# SPI_IFC.net
KiCad netlist of a schematic drawn in Altium Designer
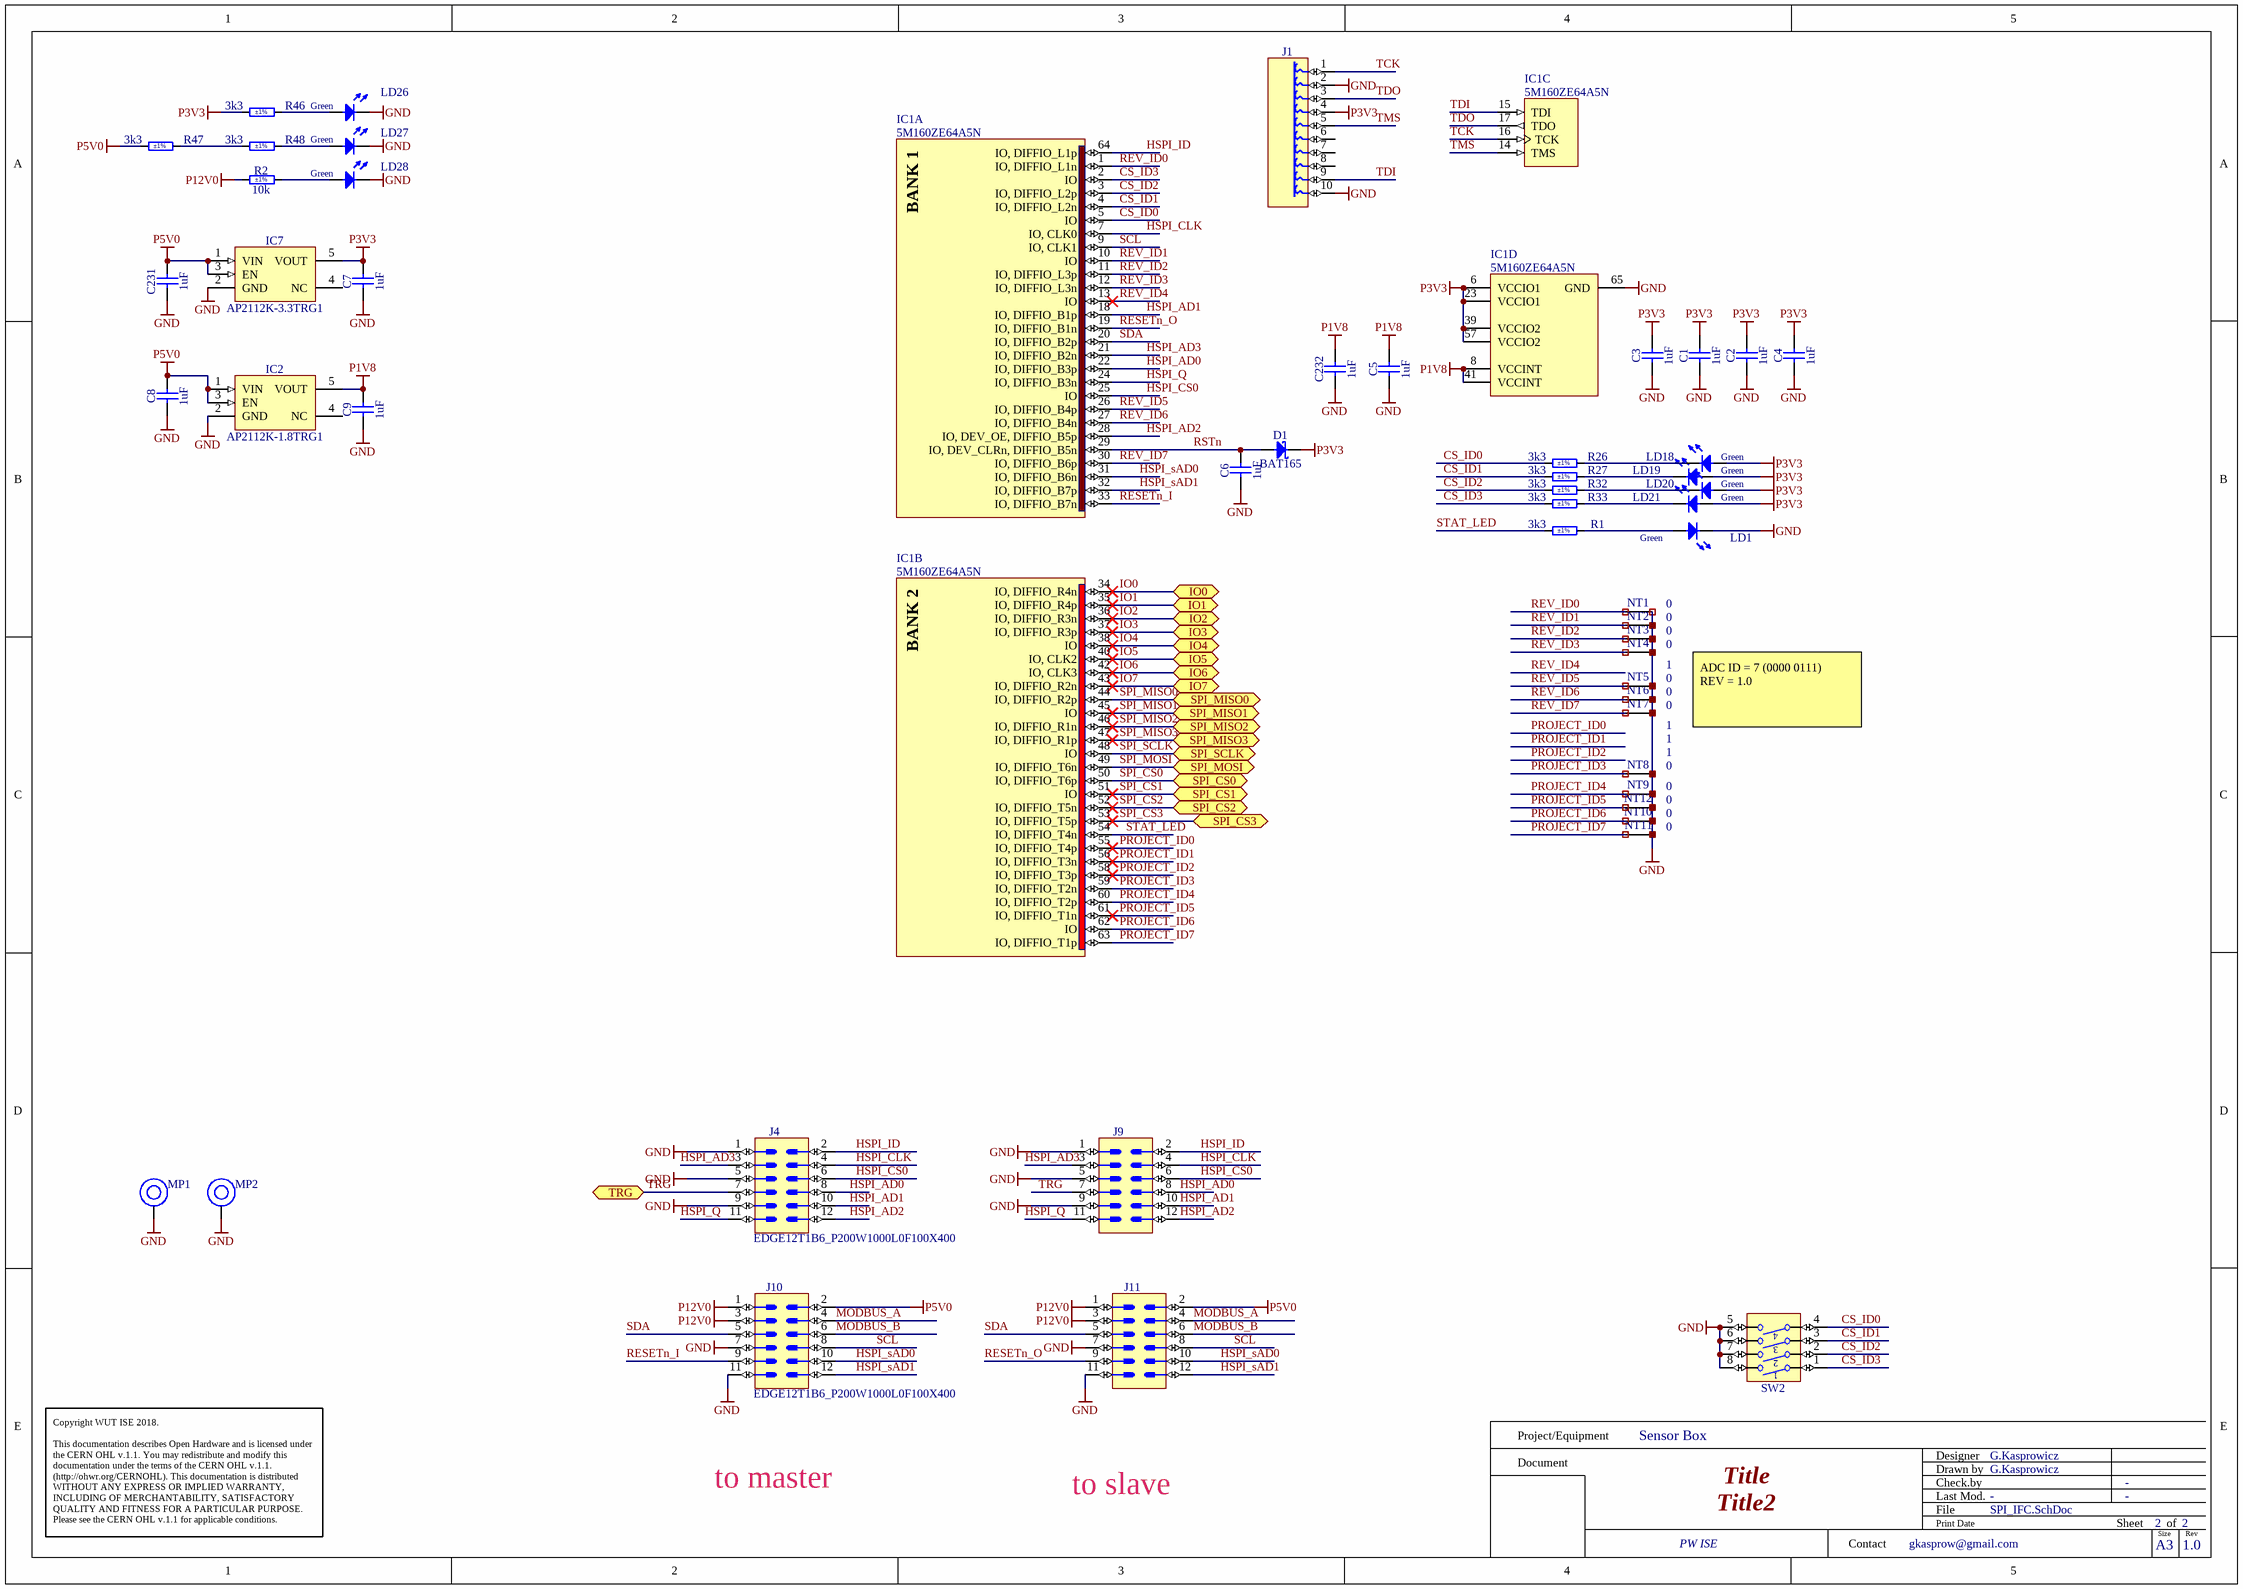
[diagram p0: SPI_IFC.SchDoc]

(export (version "E")
  (design (tool "Eeschema 10.0.6"))
  (components
    (comp (ref "C1")
      (value "1uF")
      (footprint "CAPC1005X55N")
      (description "Non-polarised capacitor")
      (fields
        (field (name "PART NUMBER") "CC0402_1UF_16V_10%_X5R")
        (field (name "VOLTAGE") "16V")
        (field (name "AUTHOR") "CERN DEM JLC")
      )
      (libsource (lib "Capacitors") (part "Capacitor - non polarized"))
    )
    (comp (ref "C2")
      (value "1uF")
      (footprint "CAPC1005X55N")
      (description "Non-polarised capacitor")
      (fields
        (field (name "PART NUMBER") "CC0402_1UF_16V_10%_X5R")
        (field (name "VOLTAGE") "16V")
        (field (name "AUTHOR") "CERN DEM JLC")
      )
      (libsource (lib "Capacitors") (part "Capacitor - non polarized"))
    )
    (comp (ref "C3")
      (value "1uF")
      (footprint "CAPC1005X55N")
      (description "Non-polarised capacitor")
      (fields
        (field (name "PART NUMBER") "CC0402_1UF_16V_10%_X5R")
        (field (name "VOLTAGE") "16V")
        (field (name "AUTHOR") "CERN DEM JLC")
      )
      (libsource (lib "Capacitors") (part "Capacitor - non polarized"))
    )
    (comp (ref "C4")
      (value "1uF")
      (footprint "CAPC1005X55N")
      (description "Non-polarised capacitor")
      (fields
        (field (name "PART NUMBER") "CC0402_1UF_16V_10%_X5R")
        (field (name "VOLTAGE") "16V")
        (field (name "AUTHOR") "CERN DEM JLC")
      )
      (libsource (lib "Capacitors") (part "Capacitor - non polarized"))
    )
    (comp (ref "C5")
      (value "1uF")
      (footprint "CAPC1005X55N")
      (description "Non-polarised capacitor")
      (fields
        (field (name "PART NUMBER") "CC0402_1UF_16V_10%_X5R")
        (field (name "VOLTAGE") "16V")
        (field (name "AUTHOR") "CERN DEM JLC")
      )
      (libsource (lib "Capacitors") (part "Capacitor - non polarized"))
    )
    (comp (ref "C6")
      (value "1uF")
      (footprint "CAPC1005X55N")
      (description "Non-polarised capacitor")
      (fields
        (field (name "PART NUMBER") "CC0402_1UF_16V_10%_X5R")
        (field (name "VOLTAGE") "16V")
        (field (name "AUTHOR") "CERN DEM JLC")
      )
      (libsource (lib "Capacitors") (part "Capacitor - non polarized"))
    )
    (comp (ref "C7")
      (value "1uF")
      (footprint "CAPC1005X55N")
      (description "Non-polarised capacitor")
      (fields
        (field (name "PART NUMBER") "CC0402_1UF_16V_10%_X5R")
        (field (name "VOLTAGE") "16V")
        (field (name "AUTHOR") "CERN DEM JLC")
      )
      (libsource (lib "Capacitors") (part "Capacitor - non polarized"))
    )
    (comp (ref "C8")
      (value "1uF")
      (footprint "CAPC1005X55N")
      (description "Non-polarised capacitor")
      (fields
        (field (name "PART NUMBER") "CC0402_1UF_16V_10%_X5R")
        (field (name "VOLTAGE") "16V")
        (field (name "AUTHOR") "CERN DEM JLC")
      )
      (libsource (lib "Capacitors") (part "Capacitor - non polarized"))
    )
    (comp (ref "C9")
      (value "1uF")
      (footprint "CAPC1005X55N")
      (description "Non-polarised capacitor")
      (fields
        (field (name "PART NUMBER") "CC0402_1UF_16V_10%_X5R")
        (field (name "VOLTAGE") "16V")
        (field (name "AUTHOR") "CERN DEM JLC")
      )
      (libsource (lib "Capacitors") (part "Capacitor - non polarized"))
    )
    (comp (ref "C231")
      (value "1uF")
      (footprint "CAPC1005X55N")
      (description "Non-polarised capacitor")
      (fields
        (field (name "PART NUMBER") "CC0402_1UF_16V_10%_X5R")
        (field (name "VOLTAGE") "16V")
        (field (name "AUTHOR") "CERN DEM JLC")
      )
      (libsource (lib "Capacitors") (part "Capacitor - non polarized"))
    )
    (comp (ref "C232")
      (value "1uF")
      (footprint "CAPC1005X55N")
      (description "Non-polarised capacitor")
      (fields
        (field (name "PART NUMBER") "CC0402_1UF_16V_10%_X5R")
        (field (name "VOLTAGE") "16V")
        (field (name "AUTHOR") "CERN DEM JLC")
      )
      (libsource (lib "Capacitors") (part "Capacitor - non polarized"))
    )
    (comp (ref "D1")
      (value "BAT165")
      (footprint "SOD2512X110N")
      (description "Schottky Diode")
      (fields
        (field (name "VOLTAGE") "40V")
        (field (name "POWER") "750mA")
        (field (name "AUTHOR") "CERN DEM JLC")
      )
      (libsource (lib "ICs And Semiconductors") (part "Diode Schottky"))
    )
    (comp (ref "IC1")
      (value "5M160ZE64A5N")
      (footprint "QFP40P900X900X120-65N-S550")
      (fields (field (name "MANUFACTURER") "ALTERA") (field (name "AUTHOR") "CERN DEM JLC"))
      (libsource (lib "ICs And Semiconductors") (part "5M160ZE64A5N"))
    )
    (comp (ref "IC2")
      (value "AP2112K-1.8TRG1")
      (footprint "SOT95P285X140-5N")
      (description "600mA CMOS Low Dropout Linear Regulator with Enable")
      (fields
        (field (name "MANUFACTURER") "DIODES INCORPORATED")
        (field (name "MANUFACTURER PART NUMBER") "AP2112K-1.8")
        (field (name "AUTHOR") "CERN DEM JLC")
      )
      (libsource (lib "ICs And Semiconductors") (part "AP2112K"))
    )
    (comp (ref "IC7")
      (value "AP2112K-3.3TRG1")
      (footprint "SOT95P285X140-5N")
      (description "600mA CMOS Low Dropout Linear Regulator with Enable")
      (fields
        (field (name "MANUFACTURER") "DIODES INCORPORATED")
        (field (name "MANUFACTURER PART NUMBER") "AP2112K-3.3")
        (field (name "AUTHOR") "CERN DEM MR")
      )
      (libsource (lib "ICs And Semiconductors") (part "AP2112K"))
    )
    (comp (ref "J1")
      (value "TC2050-IDC")
      (footprint "TC2050-IDC")
      (description "TC2030-MCP and TC2050-IDC Pad Contact")
      (fields (field (name "AUTHOR") "CERN DEM HF"))
      (libsource (lib "Eletro-mechanical") (part "TC2050-IDC"))
    )
    (comp (ref "J4")
      (value "~")
      (footprint "EDGE12T1B6_P200W1000L0F100X400")
      (description "PCB Edge Connector 12 (2x6)")
      (fields
        (field (name "PART NUMBER") "EDGE10T1B6_P200W1000L0F100X400")
        (field (name "AUTHOR") "CERN DEM MR")
      )
      (libsource (lib "Connectors") (part "PCB Edge Connector 12 (2x6)"))
    )
    (comp (ref "J9")
      (value "~")
      (footprint "EDGE12T5B10_P200W1000L0F100X400")
      (description "PCB Edge Connector 12 (2x6)")
      (fields (field (name "PART NUMBER") "EDGE12T5B10_P200W1000L0F100X400") (field (name "AUTHOR") "GK"))
      (libsource (lib "Connectors") (part "PCB Edge Connector 12 (2x6) R"))
    )
    (comp (ref "J10")
      (value "~")
      (footprint "EDGE12T1B6_P200W1000L0F100X400")
      (description "PCB Edge Connector 12 (2x6)")
      (fields
        (field (name "PART NUMBER") "EDGE10T1B6_P200W1000L0F100X400")
        (field (name "AUTHOR") "CERN DEM MR")
      )
      (libsource (lib "Connectors") (part "PCB Edge Connector 12 (2x6)"))
    )
    (comp (ref "J11")
      (value "~")
      (footprint "EDGE12T5B10_P200W1000L0F100X400")
      (description "PCB Edge Connector 12 (2x6)")
      (fields (field (name "PART NUMBER") "EDGE12T5B10_P200W1000L0F100X400") (field (name "AUTHOR") "GK"))
      (libsource (lib "Connectors") (part "PCB Edge Connector 12 (2x6) R"))
    )
    (comp (ref "LD1")
      (value "Green")
      (footprint "LED_KINGBRIGHT_KP-1608CGCK")
      (description "LED Green 1C 2A")
      (fields
        (field (name "PART NUMBER") "LED_KINGBRIGHT_KP-1608CGCK")
        (field (name "MANUFACTURER") "KINGBRIGHT")
        (field (name "AUTHOR") "CERN DEM HF")
      )
      (libsource (lib "ICs And Semiconductors") (part "LED Green 1C 2A"))
    )
    (comp (ref "LD18")
      (value "Green")
      (footprint "LED_KINGBRIGHT_KP-1608CGCK")
      (description "LED Green 1C 2A")
      (fields
        (field (name "PART NUMBER") "LED_KINGBRIGHT_KP-1608CGCK")
        (field (name "MANUFACTURER") "KINGBRIGHT")
        (field (name "AUTHOR") "CERN DEM HF")
      )
      (libsource (lib "ICs And Semiconductors") (part "LED Green 1C 2A"))
    )
    (comp (ref "LD19")
      (value "Green")
      (footprint "LED_KINGBRIGHT_KP-1608CGCK")
      (description "LED Green 1C 2A")
      (fields
        (field (name "PART NUMBER") "LED_KINGBRIGHT_KP-1608CGCK")
        (field (name "MANUFACTURER") "KINGBRIGHT")
        (field (name "AUTHOR") "CERN DEM HF")
      )
      (libsource (lib "ICs And Semiconductors") (part "LED Green 1C 2A"))
    )
    (comp (ref "LD20")
      (value "Green")
      (footprint "LED_KINGBRIGHT_KP-1608CGCK")
      (description "LED Green 1C 2A")
      (fields
        (field (name "PART NUMBER") "LED_KINGBRIGHT_KP-1608CGCK")
        (field (name "MANUFACTURER") "KINGBRIGHT")
        (field (name "AUTHOR") "CERN DEM HF")
      )
      (libsource (lib "ICs And Semiconductors") (part "LED Green 1C 2A"))
    )
    (comp (ref "LD21")
      (value "Green")
      (footprint "LED_KINGBRIGHT_KP-1608CGCK")
      (description "LED Green 1C 2A")
      (fields
        (field (name "PART NUMBER") "LED_KINGBRIGHT_KP-1608CGCK")
        (field (name "MANUFACTURER") "KINGBRIGHT")
        (field (name "AUTHOR") "CERN DEM HF")
      )
      (libsource (lib "ICs And Semiconductors") (part "LED Green 1C 2A"))
    )
    (comp (ref "LD26")
      (value "Green")
      (footprint "LED_KINGBRIGHT_KP-1608CGCK")
      (description "LED Green 1C 2A")
      (fields
        (field (name "PART NUMBER") "LED_KINGBRIGHT_KP-1608CGCK")
        (field (name "MANUFACTURER") "KINGBRIGHT")
        (field (name "AUTHOR") "CERN DEM HF")
      )
      (libsource (lib "ICs And Semiconductors") (part "LED Green 1C 2A"))
    )
    (comp (ref "LD27")
      (value "Green")
      (footprint "LED_KINGBRIGHT_KP-1608CGCK")
      (description "LED Green 1C 2A")
      (fields
        (field (name "PART NUMBER") "LED_KINGBRIGHT_KP-1608CGCK")
        (field (name "MANUFACTURER") "KINGBRIGHT")
        (field (name "AUTHOR") "CERN DEM HF")
      )
      (libsource (lib "ICs And Semiconductors") (part "LED Green 1C 2A"))
    )
    (comp (ref "LD28")
      (value "Green")
      (footprint "LED_KINGBRIGHT_KP-1608CGCK")
      (description "LED Green 1C 2A")
      (fields
        (field (name "PART NUMBER") "LED_KINGBRIGHT_KP-1608CGCK")
        (field (name "MANUFACTURER") "KINGBRIGHT")
        (field (name "AUTHOR") "CERN DEM HF")
      )
      (libsource (lib "ICs And Semiconductors") (part "LED Green 1C 2A"))
    )
    (comp (ref "MP1")
      (value "M1.6 x 3mm")
      (footprint "97730306330")
      (description "WA-SMSI SMT Steel Spacer with internal Thread Bottom closed, OD 3.3mm, M1.6 x 3mm")
      (fields
        (field (name "MANUFACTURER PART NUMBER") "97730306330R")
        (field (name "MANUFACTURER") "Wurth Elektronik")
      )
      (libsource (lib "Altium_WA-SMSI (rev22a)") (part "97730306330R"))
    )
    (comp (ref "MP2")
      (value "M1.6 x 3mm")
      (footprint "97730306330")
      (description "WA-SMSI SMT Steel Spacer with internal Thread Bottom closed, OD 3.3mm, M1.6 x 3mm")
      (fields
        (field (name "MANUFACTURER PART NUMBER") "97730306330R")
        (field (name "MANUFACTURER") "Wurth Elektronik")
      )
      (libsource (lib "Altium_WA-SMSI (rev22a)") (part "97730306330R"))
    )
    (comp (ref "NT1")
      (value "Net Tie")
      (footprint "Net Tie 3")
      (fields (field (name "PART NUMBER") "Net Tie 3") (field (name "AUTHOR") "CERN DEM HF"))
      (libsource (lib "Eletro-mechanical") (part "Net Tie_a"))
    )
    (comp (ref "NT2")
      (value "Net Tie")
      (footprint "Net Tie 3")
      (fields (field (name "PART NUMBER") "Net Tie 3") (field (name "AUTHOR") "CERN DEM HF"))
      (libsource (lib "Eletro-mechanical") (part "Net Tie_a"))
    )
    (comp (ref "NT3")
      (value "Net Tie")
      (footprint "Net Tie 3")
      (fields (field (name "PART NUMBER") "Net Tie 3") (field (name "AUTHOR") "CERN DEM HF"))
      (libsource (lib "Eletro-mechanical") (part "Net Tie_a"))
    )
    (comp (ref "NT4")
      (value "Net Tie")
      (footprint "Net Tie 3")
      (fields (field (name "PART NUMBER") "Net Tie 3") (field (name "AUTHOR") "CERN DEM HF"))
      (libsource (lib "Eletro-mechanical") (part "Net Tie_a"))
    )
    (comp (ref "NT5")
      (value "Net Tie")
      (footprint "Net Tie 3")
      (fields (field (name "PART NUMBER") "Net Tie 3") (field (name "AUTHOR") "CERN DEM HF"))
      (libsource (lib "Eletro-mechanical") (part "Net Tie_a"))
    )
    (comp (ref "NT6")
      (value "Net Tie")
      (footprint "Net Tie 3")
      (fields (field (name "PART NUMBER") "Net Tie 3") (field (name "AUTHOR") "CERN DEM HF"))
      (libsource (lib "Eletro-mechanical") (part "Net Tie_a"))
    )
    (comp (ref "NT7")
      (value "Net Tie")
      (footprint "Net Tie 3")
      (fields (field (name "PART NUMBER") "Net Tie 3") (field (name "AUTHOR") "CERN DEM HF"))
      (libsource (lib "Eletro-mechanical") (part "Net Tie_a"))
    )
    (comp (ref "NT8")
      (value "Net Tie")
      (footprint "Net Tie 3")
      (fields (field (name "PART NUMBER") "Net Tie 3") (field (name "AUTHOR") "CERN DEM HF"))
      (libsource (lib "Eletro-mechanical") (part "Net Tie_a"))
    )
    (comp (ref "NT9")
      (value "Net Tie")
      (footprint "Net Tie 3")
      (fields (field (name "PART NUMBER") "Net Tie 3") (field (name "AUTHOR") "CERN DEM HF"))
      (libsource (lib "Eletro-mechanical") (part "Net Tie_a"))
    )
    (comp (ref "NT10")
      (value "Net Tie")
      (footprint "Net Tie 3")
      (fields (field (name "PART NUMBER") "Net Tie 3") (field (name "AUTHOR") "CERN DEM HF"))
      (libsource (lib "Eletro-mechanical") (part "Net Tie_a"))
    )
    (comp (ref "NT11")
      (value "Net Tie")
      (footprint "Net Tie 3")
      (fields (field (name "PART NUMBER") "Net Tie 3") (field (name "AUTHOR") "CERN DEM HF"))
      (libsource (lib "Eletro-mechanical") (part "Net Tie_a"))
    )
    (comp (ref "NT12")
      (value "Net Tie")
      (footprint "Net Tie 3")
      (fields (field (name "PART NUMBER") "Net Tie 3") (field (name "AUTHOR") "CERN DEM HF"))
      (libsource (lib "Eletro-mechanical") (part "Net Tie_a"))
    )
    (comp (ref "R1")
      (value "3k3")
      (footprint "RESC1005X40N")
      (description "Resistor - 1%")
      (fields
        (field (name "TOLERANCE") "±1%")
        (field (name "PART NUMBER") "R0402_3K3_1%_0.0625W_100PPM")
        (field (name "POWER") "0.0625W")
        (field (name "AUTHOR") "CERN DEM JLC")
      )
      (libsource (lib "Resistors") (part "Resistor - 1%"))
    )
    (comp (ref "R2")
      (value "10k")
      (footprint "RESC1005X40N")
      (description "Resistor - 1%")
      (fields
        (field (name "TOLERANCE") "±1%")
        (field (name "PART NUMBER") "R0402_10K_1%_0.0625W_100PPM")
        (field (name "POWER") "0.0625W")
        (field (name "AUTHOR") "CERN DEM JLC")
      )
      (libsource (lib "Resistors") (part "Resistor - 1%"))
    )
    (comp (ref "R26")
      (value "3k3")
      (footprint "RESC1005X40N")
      (description "Resistor - 1%")
      (fields
        (field (name "TOLERANCE") "±1%")
        (field (name "PART NUMBER") "R0402_3K3_1%_0.0625W_100PPM")
        (field (name "POWER") "0.0625W")
        (field (name "AUTHOR") "CERN DEM JLC")
      )
      (libsource (lib "Resistors") (part "Resistor - 1%"))
    )
    (comp (ref "R27")
      (value "3k3")
      (footprint "RESC1005X40N")
      (description "Resistor - 1%")
      (fields
        (field (name "TOLERANCE") "±1%")
        (field (name "PART NUMBER") "R0402_3K3_1%_0.0625W_100PPM")
        (field (name "POWER") "0.0625W")
        (field (name "AUTHOR") "CERN DEM JLC")
      )
      (libsource (lib "Resistors") (part "Resistor - 1%"))
    )
    (comp (ref "R32")
      (value "3k3")
      (footprint "RESC1005X40N")
      (description "Resistor - 1%")
      (fields
        (field (name "TOLERANCE") "±1%")
        (field (name "PART NUMBER") "R0402_3K3_1%_0.0625W_100PPM")
        (field (name "POWER") "0.0625W")
        (field (name "AUTHOR") "CERN DEM JLC")
      )
      (libsource (lib "Resistors") (part "Resistor - 1%"))
    )
    (comp (ref "R33")
      (value "3k3")
      (footprint "RESC1005X40N")
      (description "Resistor - 1%")
      (fields
        (field (name "TOLERANCE") "±1%")
        (field (name "PART NUMBER") "R0402_3K3_1%_0.0625W_100PPM")
        (field (name "POWER") "0.0625W")
        (field (name "AUTHOR") "CERN DEM JLC")
      )
      (libsource (lib "Resistors") (part "Resistor - 1%"))
    )
    (comp (ref "R46")
      (value "3k3")
      (footprint "RESC1005X40N")
      (description "Resistor - 1%")
      (fields
        (field (name "TOLERANCE") "±1%")
        (field (name "PART NUMBER") "R0402_3K3_1%_0.0625W_100PPM")
        (field (name "POWER") "0.0625W")
        (field (name "AUTHOR") "CERN DEM JLC")
      )
      (libsource (lib "Resistors") (part "Resistor - 1%"))
    )
    (comp (ref "R47")
      (value "3k3")
      (footprint "RESC1005X40N")
      (description "Resistor - 1%")
      (fields
        (field (name "TOLERANCE") "±1%")
        (field (name "PART NUMBER") "R0402_3K3_1%_0.0625W_100PPM")
        (field (name "POWER") "0.0625W")
        (field (name "AUTHOR") "CERN DEM JLC")
      )
      (libsource (lib "Resistors") (part "Resistor - 1%"))
    )
    (comp (ref "R48")
      (value "3k3")
      (footprint "RESC1005X40N")
      (description "Resistor - 1%")
      (fields
        (field (name "TOLERANCE") "±1%")
        (field (name "PART NUMBER") "R0402_3K3_1%_0.0625W_100PPM")
        (field (name "POWER") "0.0625W")
        (field (name "AUTHOR") "CERN DEM JLC")
      )
      (libsource (lib "Resistors") (part "Resistor - 1%"))
    )
    (comp (ref "SW2")
      (value "Switch")
      (footprint "SW_OMRON_A6H-4102")
      (description "4 Ways SPST DIP Switch")
      (fields
        (field (name "PART NUMBER") "SW_OMRON_A6H-4102")
        (field (name "MANUFACTURER") "OMRON")
        (field (name "AUTHOR") "CERN DEM JLC")
      )
      (libsource (lib "Eletro-mechanical") (part "SW 4x SPST DIP Switch"))
    )
  )
  (nets
    (net (code "1") (name "/CS_ID0") (class "Default")
      (node (ref "IC1") (pin "5") (pinfunction "IO_5") (pintype "bidirectional"))
      (node (ref "R26") (pin "2") (pinfunction "2_2") (pintype "passive"))
      (node (ref "SW2") (pin "4") (pinfunction "4_4") (pintype "bidirectional"))
    )
    (net (code "2") (name "/CS_ID1") (class "Default")
      (node (ref "IC1") (pin "4") (pinfunction "IO,_DIFFIO_L2n_4") (pintype "bidirectional"))
      (node (ref "R27") (pin "2") (pinfunction "2_2") (pintype "passive"))
      (node (ref "SW2") (pin "3") (pinfunction "3_3") (pintype "bidirectional"))
    )
    (net (code "3") (name "/CS_ID2") (class "Default")
      (node (ref "IC1") (pin "3") (pinfunction "IO,_DIFFIO_L2p_3") (pintype "bidirectional"))
      (node (ref "R32") (pin "2") (pinfunction "2_2") (pintype "passive"))
      (node (ref "SW2") (pin "2") (pinfunction "2_2") (pintype "bidirectional"))
    )
    (net (code "4") (name "/CS_ID3") (class "Default")
      (node (ref "IC1") (pin "2") (pinfunction "IO_2") (pintype "bidirectional"))
      (node (ref "R33") (pin "2") (pinfunction "2_2") (pintype "passive"))
      (node (ref "SW2") (pin "1") (pinfunction "1_1") (pintype "bidirectional"))
    )
    (net (code "5") (name "/HSPI_AD0") (class "Default")
      (node (ref "IC1") (pin "22") (pinfunction "IO,_DIFFIO_B3p_22") (pintype "bidirectional"))
      (node (ref "J4") (pin "8") (pinfunction "8_8") (pintype "bidirectional"))
      (node (ref "J9") (pin "8") (pinfunction "8_8") (pintype "bidirectional"))
    )
    (net (code "6") (name "/HSPI_AD1") (class "Default")
      (node (ref "IC1") (pin "18") (pinfunction "IO,_DIFFIO_B1p_18") (pintype "bidirectional"))
      (node (ref "J4") (pin "10") (pinfunction "10_10") (pintype "bidirectional"))
      (node (ref "J9") (pin "10") (pinfunction "10_10") (pintype "bidirectional"))
    )
    (net (code "7") (name "/HSPI_AD2") (class "Default")
      (node (ref "IC1") (pin "28") (pinfunction "IO,_DEV_OE,_DIFFIO_B5p_28") (pintype "bidirectional"))
      (node (ref "J4") (pin "12") (pinfunction "12_12") (pintype "bidirectional"))
      (node (ref "J9") (pin "12") (pinfunction "12_12") (pintype "bidirectional"))
    )
    (net (code "8") (name "/HSPI_AD3") (class "Default")
      (node (ref "IC1") (pin "21") (pinfunction "IO,_DIFFIO_B2n_21") (pintype "bidirectional"))
      (node (ref "J4") (pin "3") (pinfunction "3_3") (pintype "bidirectional"))
      (node (ref "J9") (pin "3") (pinfunction "3_3") (pintype "bidirectional"))
    )
    (net (code "9") (name "/HSPI_CLK") (class "Default")
      (node (ref "IC1") (pin "7") (pinfunction "IO,_CLK0_7") (pintype "bidirectional"))
      (node (ref "J4") (pin "4") (pinfunction "4_4") (pintype "bidirectional"))
      (node (ref "J9") (pin "4") (pinfunction "4_4") (pintype "bidirectional"))
    )
    (net (code "10") (name "/HSPI_CS0") (class "Default")
      (node (ref "IC1") (pin "25") (pinfunction "IO_25") (pintype "bidirectional"))
      (node (ref "J4") (pin "6") (pinfunction "6_6") (pintype "bidirectional"))
      (node (ref "J9") (pin "6") (pinfunction "6_6") (pintype "bidirectional"))
    )
    (net (code "11") (name "/HSPI_ID") (class "Default")
      (node (ref "IC1") (pin "64") (pinfunction "IO,_DIFFIO_L1p_64") (pintype "bidirectional"))
      (node (ref "J4") (pin "2") (pinfunction "2_2") (pintype "bidirectional"))
      (node (ref "J9") (pin "2") (pinfunction "2_2") (pintype "bidirectional"))
    )
    (net (code "12") (name "/HSPI_Q") (class "Default")
      (node (ref "IC1") (pin "24") (pinfunction "IO,_DIFFIO_B3n_24") (pintype "bidirectional"))
      (node (ref "J4") (pin "11") (pinfunction "11_11") (pintype "bidirectional"))
      (node (ref "J9") (pin "11") (pinfunction "11_11") (pintype "bidirectional"))
    )
    (net (code "13") (name "/HSPI_sAD0") (class "Default")
      (node (ref "IC1") (pin "31") (pinfunction "IO,_DIFFIO_B6n_31") (pintype "bidirectional"))
      (node (ref "J10") (pin "10") (pinfunction "10_10") (pintype "bidirectional"))
      (node (ref "J11") (pin "10") (pinfunction "10_10") (pintype "bidirectional"))
    )
    (net (code "14") (name "/HSPI_sAD1") (class "Default")
      (node (ref "IC1") (pin "32") (pinfunction "IO,_DIFFIO_B7p_32") (pintype "bidirectional"))
      (node (ref "J10") (pin "12") (pinfunction "12_12") (pintype "bidirectional"))
      (node (ref "J11") (pin "12") (pinfunction "12_12") (pintype "bidirectional"))
    )
    (net (code "15") (name "/IO0") (class "Default")
      (node (ref "IC1") (pin "34") (pinfunction "IO,_DIFFIO_R4n_34") (pintype "bidirectional+no_connect"))
    )
    (net (code "16") (name "/IO1") (class "Default")
      (node (ref "IC1") (pin "35") (pinfunction "IO,_DIFFIO_R4p_35") (pintype "bidirectional+no_connect"))
    )
    (net (code "17") (name "/IO2") (class "Default")
      (node (ref "IC1") (pin "36") (pinfunction "IO,_DIFFIO_R3n_36") (pintype "bidirectional+no_connect"))
    )
    (net (code "18") (name "/IO3") (class "Default")
      (node (ref "IC1") (pin "37") (pinfunction "IO,_DIFFIO_R3p_37") (pintype "bidirectional+no_connect"))
    )
    (net (code "19") (name "/IO4") (class "Default")
      (node (ref "IC1") (pin "38") (pinfunction "IO_38") (pintype "bidirectional+no_connect"))
    )
    (net (code "20") (name "/IO5") (class "Default")
      (node (ref "IC1") (pin "40") (pinfunction "IO,_CLK2_40") (pintype "bidirectional+no_connect"))
    )
    (net (code "21") (name "/IO6") (class "Default")
      (node (ref "IC1") (pin "42") (pinfunction "IO,_CLK3_42") (pintype "bidirectional+no_connect"))
    )
    (net (code "22") (name "/IO7") (class "Default")
      (node (ref "IC1") (pin "43") (pinfunction "IO,_DIFFIO_R2n_43") (pintype "bidirectional+no_connect"))
    )
    (net (code "23") (name "/MODBUS_A") (class "Default")
      (node (ref "J10") (pin "4") (pinfunction "4_4") (pintype "bidirectional"))
      (node (ref "J11") (pin "4") (pinfunction "4_4") (pintype "bidirectional"))
    )
    (net (code "24") (name "/MODBUS_B") (class "Default")
      (node (ref "J10") (pin "6") (pinfunction "6_6") (pintype "bidirectional"))
      (node (ref "J11") (pin "6") (pinfunction "6_6") (pintype "bidirectional"))
    )
    (net (code "25") (name "/PROJECT_ID0") (class "Default")
      (node (ref "IC1") (pin "55") (pinfunction "IO,_DIFFIO_T4p_55") (pintype "bidirectional"))
    )
    (net (code "26") (name "/PROJECT_ID1") (class "Default")
      (node (ref "IC1") (pin "56") (pinfunction "IO,_DIFFIO_T3n_56") (pintype "bidirectional"))
    )
    (net (code "27") (name "/PROJECT_ID2") (class "Default")
      (node (ref "IC1") (pin "58") (pinfunction "IO,_DIFFIO_T3p_58") (pintype "bidirectional"))
    )
    (net (code "28") (name "/PROJECT_ID3") (class "Default")
      (node (ref "IC1") (pin "59") (pinfunction "IO,_DIFFIO_T2n_59") (pintype "bidirectional"))
      (node (ref "NT8") (pin "1") (pinfunction "1_1") (pintype "bidirectional"))
    )
    (net (code "29") (name "/PROJECT_ID4") (class "Default")
      (node (ref "IC1") (pin "60") (pinfunction "IO,_DIFFIO_T2p_60") (pintype "bidirectional"))
      (node (ref "NT9") (pin "1") (pinfunction "1_1") (pintype "bidirectional"))
    )
    (net (code "30") (name "/PROJECT_ID5") (class "Default")
      (node (ref "IC1") (pin "61") (pinfunction "IO,_DIFFIO_T1n_61") (pintype "bidirectional"))
      (node (ref "NT12") (pin "1") (pinfunction "1_1") (pintype "bidirectional"))
    )
    (net (code "31") (name "/PROJECT_ID6") (class "Default")
      (node (ref "IC1") (pin "62") (pinfunction "IO_62") (pintype "bidirectional"))
      (node (ref "NT10") (pin "1") (pinfunction "1_1") (pintype "bidirectional"))
    )
    (net (code "32") (name "/PROJECT_ID7") (class "Default")
      (node (ref "IC1") (pin "63") (pinfunction "IO,_DIFFIO_T1p_63") (pintype "bidirectional"))
      (node (ref "NT11") (pin "1") (pinfunction "1_1") (pintype "bidirectional"))
    )
    (net (code "33") (name "/RESETn_I") (class "Default")
      (node (ref "IC1") (pin "33") (pinfunction "IO,_DIFFIO_B7n_33") (pintype "bidirectional"))
      (node (ref "J10") (pin "9") (pinfunction "9_9") (pintype "bidirectional"))
    )
    (net (code "34") (name "/RESETn_O") (class "Default")
      (node (ref "IC1") (pin "19") (pinfunction "IO,_DIFFIO_B1n_19") (pintype "bidirectional"))
      (node (ref "J11") (pin "9") (pinfunction "9_9") (pintype "bidirectional"))
    )
    (net (code "35") (name "/REV_ID0") (class "Default")
      (node (ref "IC1") (pin "1") (pinfunction "IO,_DIFFIO_L1n_1") (pintype "bidirectional"))
      (node (ref "NT1") (pin "1") (pinfunction "1_1") (pintype "bidirectional"))
    )
    (net (code "36") (name "/REV_ID1") (class "Default")
      (node (ref "IC1") (pin "10") (pinfunction "IO_10") (pintype "bidirectional"))
      (node (ref "NT2") (pin "1") (pinfunction "1_1") (pintype "bidirectional"))
    )
    (net (code "37") (name "/REV_ID2") (class "Default")
      (node (ref "IC1") (pin "11") (pinfunction "IO,_DIFFIO_L3p_11") (pintype "bidirectional"))
      (node (ref "NT3") (pin "1") (pinfunction "1_1") (pintype "bidirectional"))
    )
    (net (code "38") (name "/REV_ID3") (class "Default")
      (node (ref "IC1") (pin "12") (pinfunction "IO,_DIFFIO_L3n_12") (pintype "bidirectional"))
      (node (ref "NT4") (pin "1") (pinfunction "1_1") (pintype "bidirectional"))
    )
    (net (code "39") (name "/REV_ID4") (class "Default")
      (node (ref "IC1") (pin "13") (pinfunction "IO_13") (pintype "bidirectional+no_connect"))
    )
    (net (code "40") (name "/REV_ID5") (class "Default")
      (node (ref "IC1") (pin "26") (pinfunction "IO,_DIFFIO_B4p_26") (pintype "bidirectional"))
      (node (ref "NT5") (pin "1") (pinfunction "1_1") (pintype "bidirectional"))
    )
    (net (code "41") (name "/REV_ID6") (class "Default")
      (node (ref "IC1") (pin "27") (pinfunction "IO,_DIFFIO_B4n_27") (pintype "bidirectional"))
      (node (ref "NT6") (pin "1") (pinfunction "1_1") (pintype "bidirectional"))
    )
    (net (code "42") (name "/REV_ID7") (class "Default")
      (node (ref "IC1") (pin "30") (pinfunction "IO,_DIFFIO_B6p_30") (pintype "bidirectional"))
      (node (ref "NT7") (pin "1") (pinfunction "1_1") (pintype "bidirectional"))
    )
    (net (code "43") (name "/RSTn") (class "Default")
      (node (ref "C6") (pin "2") (pinfunction "2_2") (pintype "passive"))
      (node (ref "D1") (pin "2") (pinfunction "A_2") (pintype "passive"))
      (node (ref "IC1") (pin "29") (pinfunction "IO,_DEV_CLRn,_DIFFIO_B5n_29") (pintype "bidirectional"))
    )
    (net (code "44") (name "/SCL") (class "Default")
      (node (ref "IC1") (pin "9") (pinfunction "IO,_CLK1_9") (pintype "bidirectional"))
      (node (ref "J10") (pin "8") (pinfunction "8_8") (pintype "bidirectional"))
      (node (ref "J11") (pin "8") (pinfunction "8_8") (pintype "bidirectional"))
    )
    (net (code "45") (name "/SDA") (class "Default")
      (node (ref "IC1") (pin "20") (pinfunction "IO,_DIFFIO_B2p_20") (pintype "bidirectional"))
      (node (ref "J10") (pin "5") (pinfunction "5_5") (pintype "bidirectional"))
      (node (ref "J11") (pin "5") (pinfunction "5_5") (pintype "bidirectional"))
    )
    (net (code "46") (name "/SPI_CS0") (class "Default")
      (node (ref "IC1") (pin "50") (pinfunction "IO,_DIFFIO_T6p_50") (pintype "bidirectional"))
    )
    (net (code "47") (name "/SPI_CS1") (class "Default")
      (node (ref "IC1") (pin "51") (pinfunction "IO_51") (pintype "bidirectional+no_connect"))
    )
    (net (code "48") (name "/SPI_CS2") (class "Default")
      (node (ref "IC1") (pin "52") (pinfunction "IO,_DIFFIO_T5n_52") (pintype "bidirectional+no_connect"))
    )
    (net (code "49") (name "/SPI_CS3") (class "Default")
      (node (ref "IC1") (pin "53") (pinfunction "IO,_DIFFIO_T5p_53") (pintype "bidirectional+no_connect"))
    )
    (net (code "50") (name "/SPI_MISO0") (class "Default")
      (node (ref "IC1") (pin "44") (pinfunction "IO,_DIFFIO_R2p_44") (pintype "bidirectional"))
    )
    (net (code "51") (name "/SPI_MISO1") (class "Default")
      (node (ref "IC1") (pin "45") (pinfunction "IO_45") (pintype "bidirectional+no_connect"))
    )
    (net (code "52") (name "/SPI_MISO2") (class "Default")
      (node (ref "IC1") (pin "46") (pinfunction "IO,_DIFFIO_R1n_46") (pintype "bidirectional+no_connect"))
    )
    (net (code "53") (name "/SPI_MISO3") (class "Default")
      (node (ref "IC1") (pin "47") (pinfunction "IO,_DIFFIO_R1p_47") (pintype "bidirectional+no_connect"))
    )
    (net (code "54") (name "/SPI_MOSI") (class "Default")
      (node (ref "IC1") (pin "49") (pinfunction "IO,_DIFFIO_T6n_49") (pintype "bidirectional"))
    )
    (net (code "55") (name "/SPI_SCLK") (class "Default")
      (node (ref "IC1") (pin "48") (pinfunction "IO_48") (pintype "bidirectional"))
    )
    (net (code "56") (name "/STAT_LED") (class "Default")
      (node (ref "IC1") (pin "54") (pinfunction "IO,_DIFFIO_T4n_54") (pintype "bidirectional"))
      (node (ref "R1") (pin "2") (pinfunction "2_2") (pintype "passive"))
    )
    (net (code "57") (name "/TCK") (class "Default")
      (node (ref "IC1") (pin "16") (pinfunction "TCK_16") (pintype "input"))
      (node (ref "J1") (pin "1") (pinfunction "1_1") (pintype "bidirectional"))
    )
    (net (code "58") (name "/TDI") (class "Default")
      (node (ref "IC1") (pin "15") (pinfunction "TDI_15") (pintype "input"))
      (node (ref "J1") (pin "9") (pinfunction "9_9") (pintype "bidirectional"))
    )
    (net (code "59") (name "/TDO") (class "Default")
      (node (ref "IC1") (pin "17") (pinfunction "TDO_17") (pintype "output"))
      (node (ref "J1") (pin "3") (pinfunction "3_3") (pintype "bidirectional"))
    )
    (net (code "60") (name "/TMS") (class "Default")
      (node (ref "IC1") (pin "14") (pinfunction "TMS_14") (pintype "input"))
      (node (ref "J1") (pin "5") (pinfunction "5_5") (pintype "bidirectional"))
    )
    (net (code "61") (name "/TRG") (class "Default")
      (node (ref "J4") (pin "7") (pinfunction "7_7") (pintype "bidirectional"))
      (node (ref "J9") (pin "7") (pinfunction "7_7") (pintype "bidirectional"))
    )
    (net (code "62") (name "GND") (class "Default")
      (node (ref "C1") (pin "1") (pinfunction "1_1") (pintype "passive"))
      (node (ref "C2") (pin "1") (pinfunction "1_1") (pintype "passive"))
      (node (ref "C231") (pin "1") (pinfunction "1_1") (pintype "passive"))
      (node (ref "C232") (pin "1") (pinfunction "1_1") (pintype "passive"))
      (node (ref "C3") (pin "1") (pinfunction "1_1") (pintype "passive"))
      (node (ref "C4") (pin "1") (pinfunction "1_1") (pintype "passive"))
      (node (ref "C5") (pin "1") (pinfunction "1_1") (pintype "passive"))
      (node (ref "C6") (pin "1") (pinfunction "1_1") (pintype "passive"))
      (node (ref "C7") (pin "1") (pinfunction "1_1") (pintype "passive"))
      (node (ref "C8") (pin "1") (pinfunction "1_1") (pintype "passive"))
      (node (ref "C9") (pin "1") (pinfunction "1_1") (pintype "passive"))
      (node (ref "IC1") (pin "65") (pinfunction "GND_65") (pintype "power_in"))
      (node (ref "IC2") (pin "2") (pinfunction "GND_2") (pintype "power_in"))
      (node (ref "IC7") (pin "2") (pinfunction "GND_2") (pintype "power_in"))
      (node (ref "J1") (pin "10") (pinfunction "10_10") (pintype "bidirectional"))
      (node (ref "J1") (pin "2") (pinfunction "2_2") (pintype "bidirectional"))
      (node (ref "J10") (pin "11") (pinfunction "11_11") (pintype "bidirectional"))
      (node (ref "J10") (pin "7") (pinfunction "7_7") (pintype "bidirectional"))
      (node (ref "J11") (pin "11") (pinfunction "11_11") (pintype "bidirectional"))
      (node (ref "J11") (pin "7") (pinfunction "7_7") (pintype "bidirectional"))
      (node (ref "J4") (pin "1") (pinfunction "1_1") (pintype "bidirectional"))
      (node (ref "J4") (pin "5") (pinfunction "5_5") (pintype "bidirectional"))
      (node (ref "J4") (pin "9") (pinfunction "9_9") (pintype "bidirectional"))
      (node (ref "J9") (pin "1") (pinfunction "1_1") (pintype "bidirectional"))
      (node (ref "J9") (pin "5") (pinfunction "5_5") (pintype "bidirectional"))
      (node (ref "J9") (pin "9") (pinfunction "9_9") (pintype "bidirectional"))
      (node (ref "LD1") (pin "1") (pinfunction "C_1") (pintype "passive"))
      (node (ref "LD26") (pin "1") (pinfunction "C_1") (pintype "passive"))
      (node (ref "LD27") (pin "1") (pinfunction "C_1") (pintype "passive"))
      (node (ref "LD28") (pin "1") (pinfunction "C_1") (pintype "passive"))
      (node (ref "MP1") (pin "1") (pinfunction "1_1") (pintype "passive"))
      (node (ref "MP2") (pin "1") (pinfunction "1_1") (pintype "passive"))
      (node (ref "NT1") (pin "2") (pinfunction "2_2") (pintype "bidirectional"))
      (node (ref "NT10") (pin "2") (pinfunction "2_2") (pintype "bidirectional"))
      (node (ref "NT11") (pin "2") (pinfunction "2_2") (pintype "bidirectional"))
      (node (ref "NT12") (pin "2") (pinfunction "2_2") (pintype "bidirectional"))
      (node (ref "NT2") (pin "2") (pinfunction "2_2") (pintype "bidirectional"))
      (node (ref "NT3") (pin "2") (pinfunction "2_2") (pintype "bidirectional"))
      (node (ref "NT4") (pin "2") (pinfunction "2_2") (pintype "bidirectional"))
      (node (ref "NT5") (pin "2") (pinfunction "2_2") (pintype "bidirectional"))
      (node (ref "NT6") (pin "2") (pinfunction "2_2") (pintype "bidirectional"))
      (node (ref "NT7") (pin "2") (pinfunction "2_2") (pintype "bidirectional"))
      (node (ref "NT8") (pin "2") (pinfunction "2_2") (pintype "bidirectional"))
      (node (ref "NT9") (pin "2") (pinfunction "2_2") (pintype "bidirectional"))
      (node (ref "SW2") (pin "5") (pinfunction "5_5") (pintype "bidirectional"))
      (node (ref "SW2") (pin "6") (pinfunction "6_6") (pintype "bidirectional"))
      (node (ref "SW2") (pin "7") (pinfunction "7_7") (pintype "bidirectional"))
      (node (ref "SW2") (pin "8") (pinfunction "8_8") (pintype "bidirectional"))
    )
    (net (code "63") (name "Net-(LD1-A)") (class "Default")
      (node (ref "LD1") (pin "2") (pinfunction "A_2") (pintype "passive"))
      (node (ref "R1") (pin "1") (pinfunction "1_1") (pintype "passive"))
    )
    (net (code "64") (name "Net-(LD18-C)") (class "Default")
      (node (ref "LD18") (pin "1") (pinfunction "C_1") (pintype "passive"))
      (node (ref "R26") (pin "1") (pinfunction "1_1") (pintype "passive"))
    )
    (net (code "65") (name "Net-(LD19-C)") (class "Default")
      (node (ref "LD19") (pin "1") (pinfunction "C_1") (pintype "passive"))
      (node (ref "R27") (pin "1") (pinfunction "1_1") (pintype "passive"))
    )
    (net (code "66") (name "Net-(LD20-C)") (class "Default")
      (node (ref "LD20") (pin "1") (pinfunction "C_1") (pintype "passive"))
      (node (ref "R32") (pin "1") (pinfunction "1_1") (pintype "passive"))
    )
    (net (code "67") (name "Net-(LD21-C)") (class "Default")
      (node (ref "LD21") (pin "1") (pinfunction "C_1") (pintype "passive"))
      (node (ref "R33") (pin "1") (pinfunction "1_1") (pintype "passive"))
    )
    (net (code "68") (name "Net-(LD26-A)") (class "Default")
      (node (ref "LD26") (pin "2") (pinfunction "A_2") (pintype "passive"))
      (node (ref "R46") (pin "1") (pinfunction "1_1") (pintype "passive"))
    )
    (net (code "69") (name "Net-(LD27-A)") (class "Default")
      (node (ref "LD27") (pin "2") (pinfunction "A_2") (pintype "passive"))
      (node (ref "R48") (pin "1") (pinfunction "1_1") (pintype "passive"))
    )
    (net (code "70") (name "Net-(LD28-A)") (class "Default")
      (node (ref "LD28") (pin "2") (pinfunction "A_2") (pintype "passive"))
      (node (ref "R2") (pin "2") (pinfunction "2_2") (pintype "passive"))
    )
    (net (code "71") (name "Net-(R47-Pad1)") (class "Default")
      (node (ref "R47") (pin "1") (pinfunction "1_1") (pintype "passive"))
      (node (ref "R48") (pin "2") (pinfunction "2_2") (pintype "passive"))
    )
    (net (code "72") (name "P1V8") (class "Default")
      (node (ref "C232") (pin "2") (pinfunction "2_2") (pintype "passive"))
      (node (ref "C5") (pin "2") (pinfunction "2_2") (pintype "passive"))
      (node (ref "C9") (pin "2") (pinfunction "2_2") (pintype "passive"))
      (node (ref "IC1") (pin "41") (pinfunction "VCCINT_41") (pintype "power_in"))
      (node (ref "IC1") (pin "8") (pinfunction "VCCINT_8") (pintype "power_in"))
      (node (ref "IC2") (pin "5") (pinfunction "VOUT_5") (pintype "power_in"))
    )
    (net (code "73") (name "P3V3") (class "Default")
      (node (ref "C1") (pin "2") (pinfunction "2_2") (pintype "passive"))
      (node (ref "C2") (pin "2") (pinfunction "2_2") (pintype "passive"))
      (node (ref "C3") (pin "2") (pinfunction "2_2") (pintype "passive"))
      (node (ref "C4") (pin "2") (pinfunction "2_2") (pintype "passive"))
      (node (ref "C7") (pin "2") (pinfunction "2_2") (pintype "passive"))
      (node (ref "D1") (pin "1") (pinfunction "C_1") (pintype "passive"))
      (node (ref "IC1") (pin "23") (pinfunction "VCCIO1_23") (pintype "power_in"))
      (node (ref "IC1") (pin "39") (pinfunction "VCCIO2_39") (pintype "power_in"))
      (node (ref "IC1") (pin "57") (pinfunction "VCCIO2_57") (pintype "power_in"))
      (node (ref "IC1") (pin "6") (pinfunction "VCCIO1_6") (pintype "power_in"))
      (node (ref "IC7") (pin "5") (pinfunction "VOUT_5") (pintype "power_in"))
      (node (ref "J1") (pin "4") (pinfunction "4_4") (pintype "bidirectional"))
      (node (ref "LD18") (pin "2") (pinfunction "A_2") (pintype "passive"))
      (node (ref "LD19") (pin "2") (pinfunction "A_2") (pintype "passive"))
      (node (ref "LD20") (pin "2") (pinfunction "A_2") (pintype "passive"))
      (node (ref "LD21") (pin "2") (pinfunction "A_2") (pintype "passive"))
      (node (ref "R46") (pin "2") (pinfunction "2_2") (pintype "passive"))
    )
    (net (code "74") (name "P5V0") (class "Default")
      (node (ref "C231") (pin "2") (pinfunction "2_2") (pintype "passive"))
      (node (ref "C8") (pin "2") (pinfunction "2_2") (pintype "passive"))
      (node (ref "IC2") (pin "1") (pinfunction "VIN_1") (pintype "input"))
      (node (ref "IC2") (pin "3") (pinfunction "EN_3") (pintype "input"))
      (node (ref "IC7") (pin "1") (pinfunction "VIN_1") (pintype "input"))
      (node (ref "IC7") (pin "3") (pinfunction "EN_3") (pintype "input"))
      (node (ref "J10") (pin "2") (pinfunction "2_2") (pintype "bidirectional"))
      (node (ref "J11") (pin "2") (pinfunction "2_2") (pintype "bidirectional"))
      (node (ref "R47") (pin "2") (pinfunction "2_2") (pintype "passive"))
    )
    (net (code "75") (name "P12V0") (class "Default")
      (node (ref "J10") (pin "1") (pinfunction "1_1") (pintype "bidirectional"))
      (node (ref "J10") (pin "3") (pinfunction "3_3") (pintype "bidirectional"))
      (node (ref "J11") (pin "1") (pinfunction "1_1") (pintype "bidirectional"))
      (node (ref "J11") (pin "3") (pinfunction "3_3") (pintype "bidirectional"))
      (node (ref "R2") (pin "1") (pinfunction "1_1") (pintype "passive"))
    )
    (net (code "76") (name "unconnected-(IC2-NC-Pad4)") (class "Default")
      (node (ref "IC2") (pin "4") (pinfunction "NC_4") (pintype "passive"))
    )
    (net (code "77") (name "unconnected-(IC7-NC-Pad4)") (class "Default")
      (node (ref "IC7") (pin "4") (pinfunction "NC_4") (pintype "passive"))
    )
    (net (code "78") (name "unconnected-(J1-Pad6)") (class "Default")
      (node (ref "J1") (pin "6") (pinfunction "6_6") (pintype "bidirectional"))
    )
    (net (code "79") (name "unconnected-(J1-Pad7)") (class "Default")
      (node (ref "J1") (pin "7") (pinfunction "7_7") (pintype "bidirectional"))
    )
    (net (code "80") (name "unconnected-(J1-Pad8)") (class "Default")
      (node (ref "J1") (pin "8") (pinfunction "8_8") (pintype "bidirectional"))
    )
  )
)
